# TS_OD.net
KiCad netlist of a schematic drawn in EAGLE
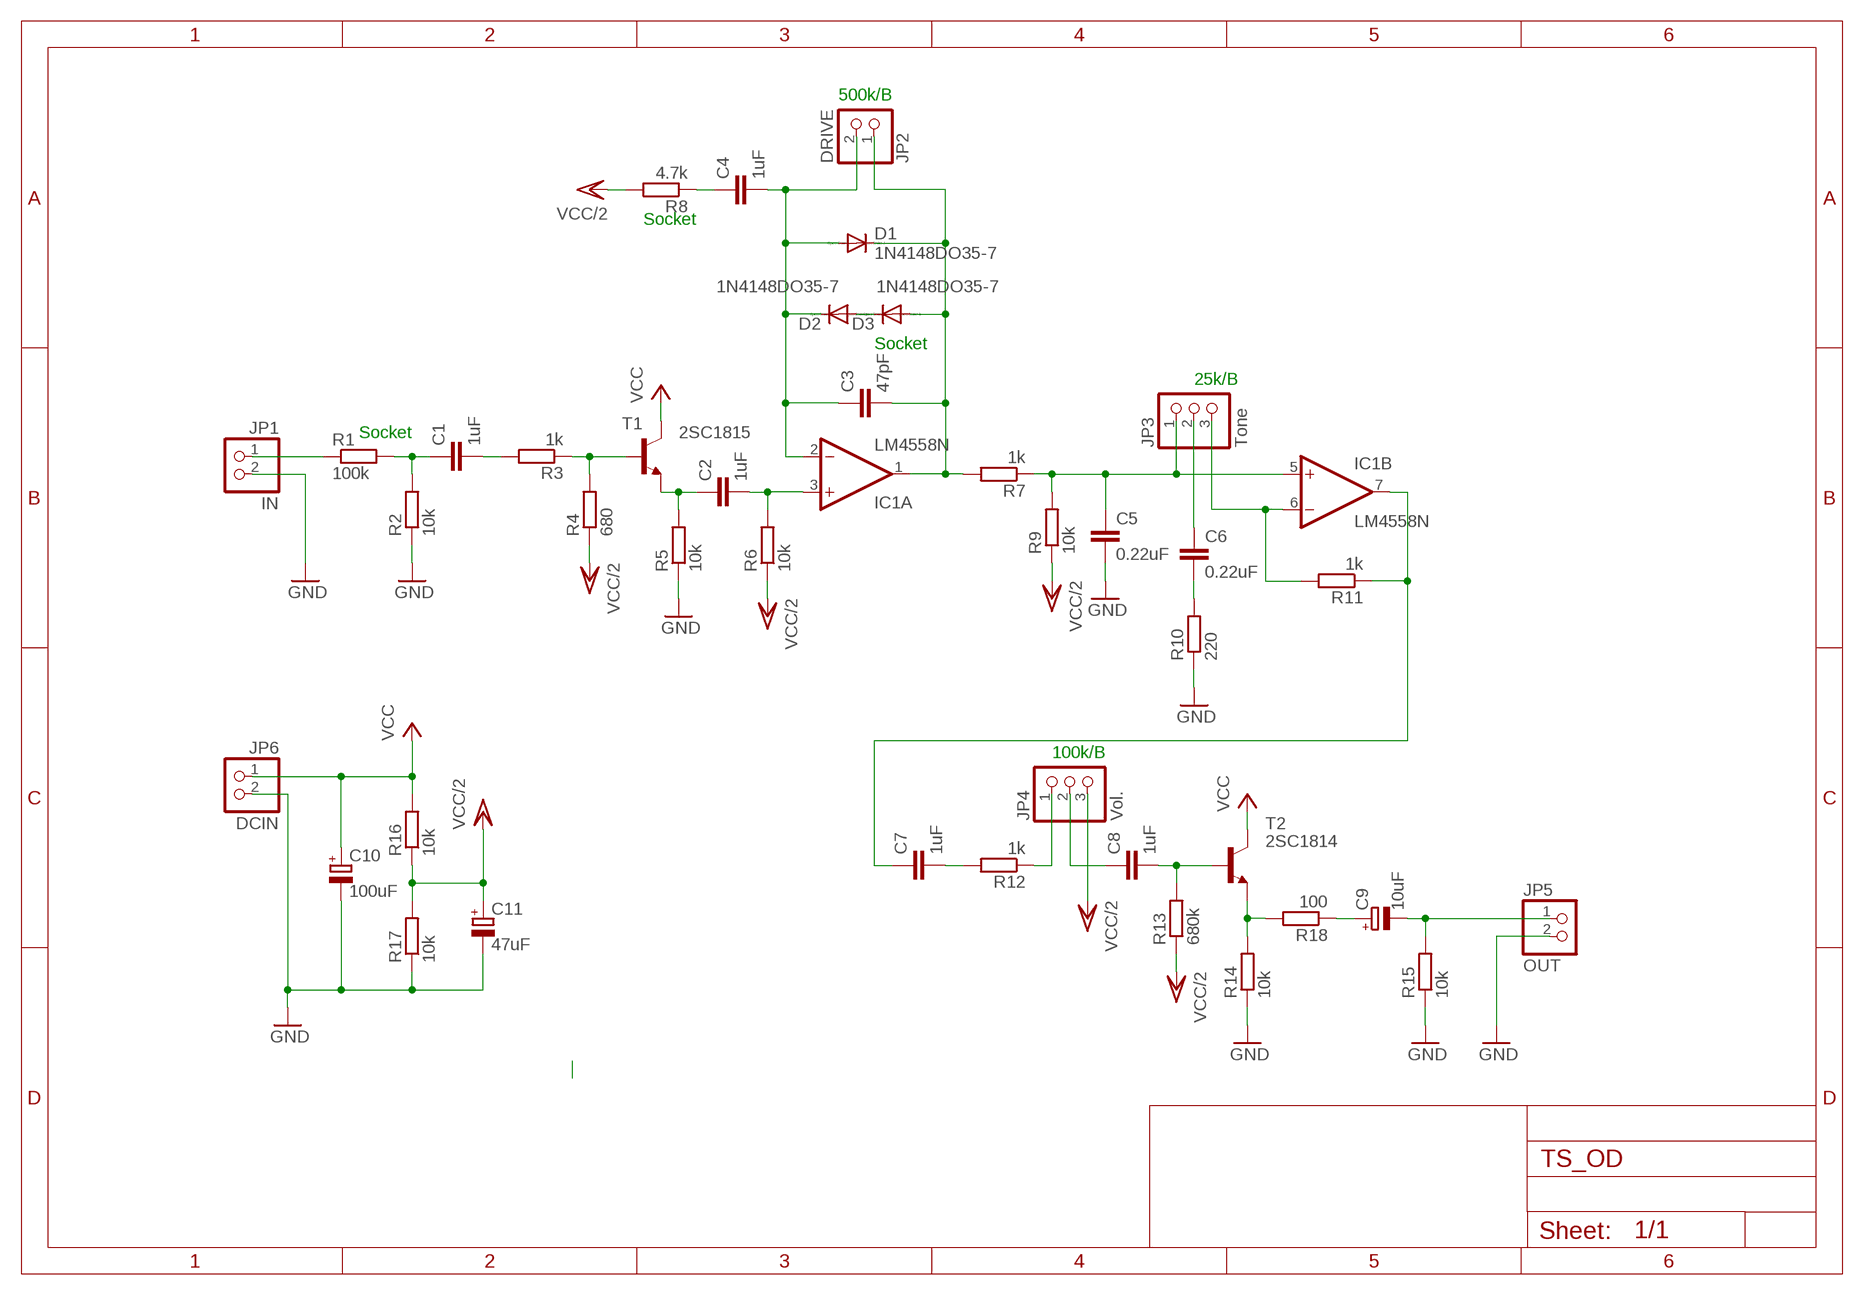
[diagram p0: schematic, sheet 1]

(export (version "E")
  (design (tool "Eeschema 10.0.6"))
  (components
    (comp (ref "C1")
      (value "1uF")
      (footprint "eagle-import:C050-050X075")
      (libsource (lib "eagle-import") (part "C-EU050-050X075"))
    )
    (comp (ref "C2")
      (value "1uF")
      (footprint "eagle-import:C050-050X075")
      (libsource (lib "eagle-import") (part "C-EU050-050X075"))
    )
    (comp (ref "C3")
      (value "47pF")
      (footprint "eagle-import:C050-024X044")
      (libsource (lib "eagle-import") (part "C-EU050-024X044"))
    )
    (comp (ref "C4")
      (value "1uF")
      (footprint "eagle-import:C050-050X075")
      (libsource (lib "eagle-import") (part "C-EU050-050X075"))
    )
    (comp (ref "C5")
      (value "0.22uF")
      (footprint "eagle-import:C050-035X075")
      (libsource (lib "eagle-import") (part "C-EU050-035X075"))
    )
    (comp (ref "C6")
      (value "0.22uF")
      (footprint "eagle-import:C050-035X075")
      (libsource (lib "eagle-import") (part "C-EU050-035X075"))
    )
    (comp (ref "C7")
      (value "1uF")
      (footprint "eagle-import:C050-050X075")
      (libsource (lib "eagle-import") (part "C-EU050-050X075"))
    )
    (comp (ref "C8")
      (value "1uF")
      (footprint "eagle-import:C050-050X075")
      (libsource (lib "eagle-import") (part "C-EU050-050X075"))
    )
    (comp (ref "C9")
      (value "10uF")
      (footprint "eagle-import:E2,5-5")
      (libsource (lib "eagle-import") (part "CPOL-EUE2.5-5"))
    )
    (comp (ref "C10")
      (value "100uF")
      (footprint "eagle-import:E2,5-7")
      (libsource (lib "eagle-import") (part "CPOL-EUE2.5-7"))
    )
    (comp (ref "C11")
      (value "47uF")
      (footprint "eagle-import:E2,5-7")
      (libsource (lib "eagle-import") (part "CPOL-EUE2.5-7"))
    )
    (comp (ref "D1")
      (value "1N4148DO35-7")
      (footprint "eagle-import:DO35-7")
      (libsource (lib "eagle-import") (part "1N4148DO35-7"))
    )
    (comp (ref "D2")
      (value "1N4148DO35-7")
      (footprint "eagle-import:DO35-7")
      (libsource (lib "eagle-import") (part "1N4148DO35-7"))
    )
    (comp (ref "D3")
      (value "1N4148DO35-7")
      (footprint "eagle-import:DO35-7")
      (libsource (lib "eagle-import") (part "1N4148DO35-7"))
    )
    (comp (ref "IC1")
      (value "LM4558N")
      (footprint "eagle-import:DIL08")
      (libsource (lib "eagle-import") (part "4558NLM"))
    )
    (comp (ref "JP1")
      (value "IN")
      (footprint "eagle-import:1X02")
      (libsource (lib "eagle-import") (part "PINHD-1X2"))
    )
    (comp (ref "JP2")
      (value "DRIVE")
      (footprint "eagle-import:1X02")
      (libsource (lib "eagle-import") (part "PINHD-1X2"))
    )
    (comp (ref "JP3")
      (value "Tone")
      (footprint "eagle-import:1X03")
      (libsource (lib "eagle-import") (part "PINHD-1X3"))
    )
    (comp (ref "JP4")
      (value "Vol.")
      (footprint "eagle-import:1X03")
      (libsource (lib "eagle-import") (part "PINHD-1X3"))
    )
    (comp (ref "JP5")
      (value "OUT")
      (footprint "eagle-import:1X02")
      (libsource (lib "eagle-import") (part "PINHD-1X2"))
    )
    (comp (ref "JP6")
      (value "DCIN")
      (footprint "eagle-import:1X02")
      (libsource (lib "eagle-import") (part "PINHD-1X2"))
    )
    (comp (ref "R1")
      (value "100k")
      (footprint "eagle-import:0207_7")
      (libsource (lib "eagle-import") (part "R-EU_0207/7"))
    )
    (comp (ref "R2")
      (value "10k")
      (footprint "eagle-import:0207_7")
      (libsource (lib "eagle-import") (part "R-EU_0207/7"))
    )
    (comp (ref "R3")
      (value "1k")
      (footprint "eagle-import:0207_7")
      (libsource (lib "eagle-import") (part "R-EU_0207/7"))
    )
    (comp (ref "R4")
      (value "680")
      (footprint "eagle-import:0207_7")
      (libsource (lib "eagle-import") (part "R-EU_0207/7"))
    )
    (comp (ref "R5")
      (value "10k")
      (footprint "eagle-import:0207_7")
      (libsource (lib "eagle-import") (part "R-EU_0207/7"))
    )
    (comp (ref "R6")
      (value "10k")
      (footprint "eagle-import:0207_7")
      (libsource (lib "eagle-import") (part "R-EU_0207/7"))
    )
    (comp (ref "R7")
      (value "1k")
      (footprint "eagle-import:0207_7")
      (libsource (lib "eagle-import") (part "R-EU_0207/7"))
    )
    (comp (ref "R8")
      (value "4.7k")
      (footprint "eagle-import:0207_7")
      (libsource (lib "eagle-import") (part "R-EU_0207/7"))
    )
    (comp (ref "R9")
      (value "10k")
      (footprint "eagle-import:0207_7")
      (libsource (lib "eagle-import") (part "R-EU_0207/7"))
    )
    (comp (ref "R10")
      (value "220")
      (footprint "eagle-import:0207_7")
      (libsource (lib "eagle-import") (part "R-EU_0207/7"))
    )
    (comp (ref "R11")
      (value "1k")
      (footprint "eagle-import:0207_7")
      (libsource (lib "eagle-import") (part "R-EU_0207/7"))
    )
    (comp (ref "R12")
      (value "1k")
      (footprint "eagle-import:0207_7")
      (libsource (lib "eagle-import") (part "R-EU_0207/7"))
    )
    (comp (ref "R13")
      (value "680k")
      (footprint "eagle-import:0207_7")
      (libsource (lib "eagle-import") (part "R-EU_0207/7"))
    )
    (comp (ref "R14")
      (value "10k")
      (footprint "eagle-import:0207_7")
      (libsource (lib "eagle-import") (part "R-EU_0207/7"))
    )
    (comp (ref "R15")
      (value "10k")
      (footprint "eagle-import:0207_7")
      (libsource (lib "eagle-import") (part "R-EU_0207/7"))
    )
    (comp (ref "R16")
      (value "10k")
      (footprint "eagle-import:0207_7")
      (libsource (lib "eagle-import") (part "R-EU_0207/7"))
    )
    (comp (ref "R17")
      (value "10k")
      (footprint "eagle-import:0207_7")
      (libsource (lib "eagle-import") (part "R-EU_0207/7"))
    )
    (comp (ref "R18")
      (value "100")
      (footprint "eagle-import:0207_7")
      (libsource (lib "eagle-import") (part "R-EU_0207/7"))
    )
    (comp (ref "T1")
      (value "2SC1815")
      (footprint "eagle-import:TO92-ECB")
      (libsource (lib "eagle-import") (part "-NPN-TO92-ECB"))
    )
    (comp (ref "T2")
      (value "2SC1814")
      (footprint "eagle-import:TO92-ECB")
      (libsource (lib "eagle-import") (part "-NPN-TO92-ECB"))
    )
  )
  (nets
    (net (code "1") (name "GND") (class "Default")
      (node (ref "C10") (pin "-") (pinfunction "-_-") (pintype "passive"))
      (node (ref "C11") (pin "-") (pinfunction "-_-") (pintype "passive"))
      (node (ref "C5") (pin "2") (pinfunction "2_2") (pintype "passive"))
      (node (ref "JP1") (pin "2") (pinfunction "2_2") (pintype "passive"))
      (node (ref "JP5") (pin "2") (pinfunction "2_2") (pintype "passive"))
      (node (ref "JP6") (pin "2") (pinfunction "2_2") (pintype "passive"))
      (node (ref "R10") (pin "1") (pinfunction "1_1") (pintype "passive"))
      (node (ref "R14") (pin "1") (pinfunction "1_1") (pintype "passive"))
      (node (ref "R15") (pin "1") (pinfunction "1_1") (pintype "passive"))
      (node (ref "R17") (pin "1") (pinfunction "1_1") (pintype "passive"))
      (node (ref "R2") (pin "1") (pinfunction "1_1") (pintype "passive"))
      (node (ref "R5") (pin "1") (pinfunction "1_1") (pintype "passive"))
    )
    (net (code "2") (name "Net-(C1-Pad1)") (class "Default")
      (node (ref "C1") (pin "1") (pinfunction "1_1") (pintype "passive"))
      (node (ref "R1") (pin "2") (pinfunction "2_2") (pintype "passive"))
      (node (ref "R2") (pin "2") (pinfunction "2_2") (pintype "passive"))
    )
    (net (code "3") (name "Net-(C1-Pad2)") (class "Default")
      (node (ref "C1") (pin "2") (pinfunction "2_2") (pintype "passive"))
      (node (ref "R3") (pin "2") (pinfunction "2_2") (pintype "passive"))
    )
    (net (code "4") (name "Net-(C2-Pad1)") (class "Default")
      (node (ref "C2") (pin "1") (pinfunction "1_1") (pintype "passive"))
      (node (ref "R5") (pin "2") (pinfunction "2_2") (pintype "passive"))
      (node (ref "T1") (pin "E") (pinfunction "E_E") (pintype "passive"))
    )
    (net (code "5") (name "Net-(C4-Pad1)") (class "Default")
      (node (ref "C4") (pin "1") (pinfunction "1_1") (pintype "passive"))
      (node (ref "R8") (pin "1") (pinfunction "1_1") (pintype "passive"))
    )
    (net (code "6") (name "Net-(C6-Pad1)") (class "Default")
      (node (ref "C6") (pin "1") (pinfunction "1_1") (pintype "passive"))
      (node (ref "JP3") (pin "2") (pinfunction "2_2") (pintype "passive"))
    )
    (net (code "7") (name "Net-(C6-Pad2)") (class "Default")
      (node (ref "C6") (pin "2") (pinfunction "2_2") (pintype "passive"))
      (node (ref "R10") (pin "2") (pinfunction "2_2") (pintype "passive"))
    )
    (net (code "8") (name "Net-(C7-Pad2)") (class "Default")
      (node (ref "C7") (pin "2") (pinfunction "2_2") (pintype "passive"))
      (node (ref "R12") (pin "2") (pinfunction "2_2") (pintype "passive"))
    )
    (net (code "9") (name "Net-(C8-Pad1)") (class "Default")
      (node (ref "C8") (pin "1") (pinfunction "1_1") (pintype "passive"))
      (node (ref "JP4") (pin "2") (pinfunction "2_2") (pintype "passive"))
    )
    (net (code "10") (name "Net-(C8-Pad2)") (class "Default")
      (node (ref "C8") (pin "2") (pinfunction "2_2") (pintype "passive"))
      (node (ref "R13") (pin "2") (pinfunction "2_2") (pintype "passive"))
      (node (ref "T2") (pin "B") (pinfunction "B_B") (pintype "passive"))
    )
    (net (code "11") (name "Net-(C9-Pad+)") (class "Default")
      (node (ref "C9") (pin "+") (pinfunction "+_+") (pintype "passive"))
      (node (ref "R18") (pin "1") (pinfunction "1_1") (pintype "passive"))
    )
    (net (code "12") (name "Net-(C9-Pad-)") (class "Default")
      (node (ref "C9") (pin "-") (pinfunction "-_-") (pintype "passive"))
      (node (ref "JP5") (pin "1") (pinfunction "1_1") (pintype "passive"))
      (node (ref "R15") (pin "2") (pinfunction "2_2") (pintype "passive"))
    )
    (net (code "13") (name "Net-(D2-PadA)") (class "Default")
      (node (ref "D2") (pin "A") (pinfunction "A_A") (pintype "passive"))
      (node (ref "D3") (pin "C") (pinfunction "C_C") (pintype "passive"))
    )
    (net (code "14") (name "Net-(IC1A-+IN)") (class "Default")
      (node (ref "C2") (pin "2") (pinfunction "2_2") (pintype "passive"))
      (node (ref "IC1") (pin "3") (pinfunction "+IN_3") (pintype "input"))
      (node (ref "R6") (pin "2") (pinfunction "2_2") (pintype "passive"))
    )
    (net (code "15") (name "Net-(IC1A--IN)") (class "Default")
      (node (ref "C3") (pin "1") (pinfunction "1_1") (pintype "passive"))
      (node (ref "C4") (pin "2") (pinfunction "2_2") (pintype "passive"))
      (node (ref "D1") (pin "A") (pinfunction "A_A") (pintype "passive"))
      (node (ref "D2") (pin "C") (pinfunction "C_C") (pintype "passive"))
      (node (ref "IC1") (pin "2") (pinfunction "-IN_2") (pintype "input"))
      (node (ref "JP2") (pin "2") (pinfunction "2_2") (pintype "passive"))
    )
    (net (code "16") (name "Net-(IC1A-OUT)") (class "Default")
      (node (ref "C3") (pin "2") (pinfunction "2_2") (pintype "passive"))
      (node (ref "D1") (pin "C") (pinfunction "C_C") (pintype "passive"))
      (node (ref "D3") (pin "A") (pinfunction "A_A") (pintype "passive"))
      (node (ref "IC1") (pin "1") (pinfunction "OUT_1") (pintype "output"))
      (node (ref "JP2") (pin "1") (pinfunction "1_1") (pintype "passive"))
      (node (ref "R7") (pin "2") (pinfunction "2_2") (pintype "passive"))
    )
    (net (code "17") (name "Net-(IC1B-+IN)") (class "Default")
      (node (ref "C5") (pin "1") (pinfunction "1_1") (pintype "passive"))
      (node (ref "IC1") (pin "5") (pinfunction "+IN_5") (pintype "input"))
      (node (ref "JP3") (pin "1") (pinfunction "1_1") (pintype "passive"))
      (node (ref "R7") (pin "1") (pinfunction "1_1") (pintype "passive"))
      (node (ref "R9") (pin "2") (pinfunction "2_2") (pintype "passive"))
    )
    (net (code "18") (name "Net-(IC1B--IN)") (class "Default")
      (node (ref "IC1") (pin "6") (pinfunction "-IN_6") (pintype "input"))
      (node (ref "JP3") (pin "3") (pinfunction "3_3") (pintype "passive"))
      (node (ref "R11") (pin "2") (pinfunction "2_2") (pintype "passive"))
    )
    (net (code "19") (name "Net-(IC1B-OUT)") (class "Default")
      (node (ref "C7") (pin "1") (pinfunction "1_1") (pintype "passive"))
      (node (ref "IC1") (pin "7") (pinfunction "OUT_7") (pintype "output"))
      (node (ref "R11") (pin "1") (pinfunction "1_1") (pintype "passive"))
    )
    (net (code "20") (name "Net-(JP1-Pad1)") (class "Default")
      (node (ref "JP1") (pin "1") (pinfunction "1_1") (pintype "passive"))
      (node (ref "R1") (pin "1") (pinfunction "1_1") (pintype "passive"))
    )
    (net (code "21") (name "Net-(JP4-Pad1)") (class "Default")
      (node (ref "JP4") (pin "1") (pinfunction "1_1") (pintype "passive"))
      (node (ref "R12") (pin "1") (pinfunction "1_1") (pintype "passive"))
    )
    (net (code "22") (name "Net-(R3-Pad1)") (class "Default")
      (node (ref "R3") (pin "1") (pinfunction "1_1") (pintype "passive"))
      (node (ref "R4") (pin "2") (pinfunction "2_2") (pintype "passive"))
      (node (ref "T1") (pin "B") (pinfunction "B_B") (pintype "passive"))
    )
    (net (code "23") (name "Net-(R14-Pad2)") (class "Default")
      (node (ref "R14") (pin "2") (pinfunction "2_2") (pintype "passive"))
      (node (ref "R18") (pin "2") (pinfunction "2_2") (pintype "passive"))
      (node (ref "T2") (pin "E") (pinfunction "E_E") (pintype "passive"))
    )
    (net (code "24") (name "VCC") (class "Default")
      (node (ref "C10") (pin "+") (pinfunction "+_+") (pintype "passive"))
      (node (ref "JP6") (pin "1") (pinfunction "1_1") (pintype "passive"))
      (node (ref "R16") (pin "2") (pinfunction "2_2") (pintype "passive"))
      (node (ref "T1") (pin "C") (pinfunction "C_C") (pintype "passive"))
      (node (ref "T2") (pin "C") (pinfunction "C_C") (pintype "passive"))
    )
    (net (code "25") (name "VCC{slash}2") (class "Default")
      (node (ref "C11") (pin "+") (pinfunction "+_+") (pintype "passive"))
      (node (ref "JP4") (pin "3") (pinfunction "3_3") (pintype "passive"))
      (node (ref "R13") (pin "1") (pinfunction "1_1") (pintype "passive"))
      (node (ref "R16") (pin "1") (pinfunction "1_1") (pintype "passive"))
      (node (ref "R17") (pin "2") (pinfunction "2_2") (pintype "passive"))
      (node (ref "R4") (pin "1") (pinfunction "1_1") (pintype "passive"))
      (node (ref "R6") (pin "1") (pinfunction "1_1") (pintype "passive"))
      (node (ref "R8") (pin "2") (pinfunction "2_2") (pintype "passive"))
      (node (ref "R9") (pin "1") (pinfunction "1_1") (pintype "passive"))
    )
  )
)
